# QCopterCAM_MCU_Sch.net
KiCad netlist of a schematic drawn in Altium Designer
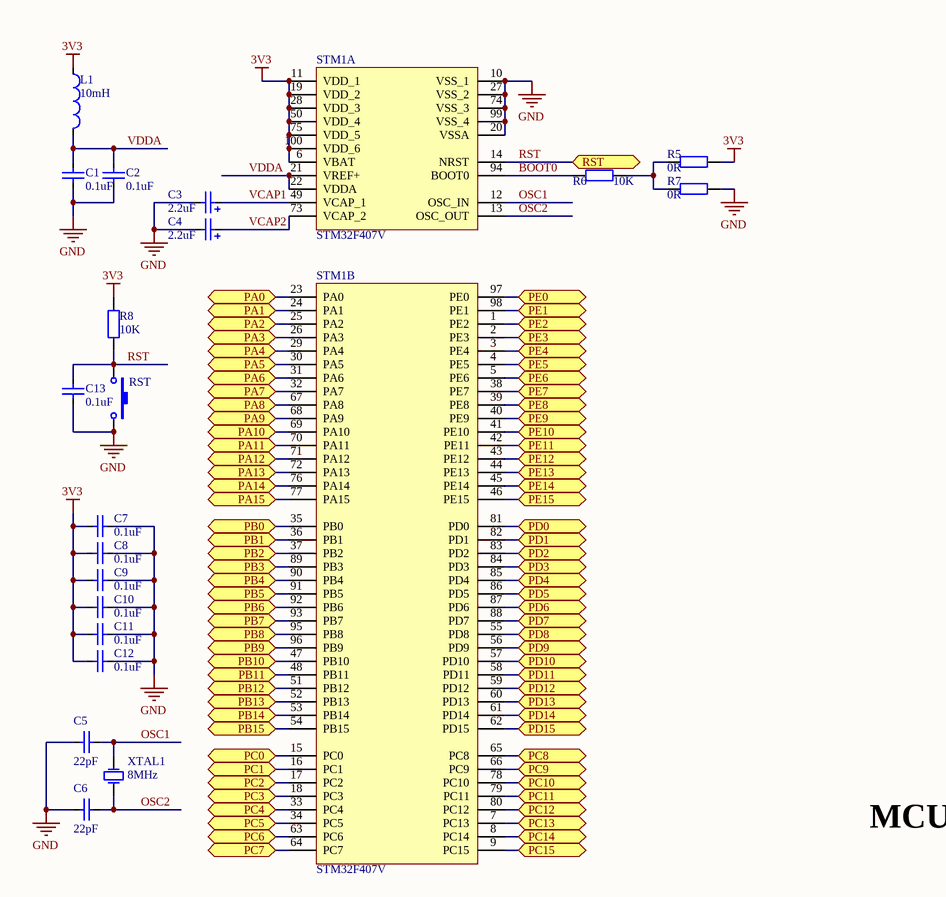
[diagram p0: QCopterCAM_MCU_Sch.SchDoc]

(export (version "E")
  (design (tool "Eeschema 10.0.6"))
  (components
    (comp (ref "C1")
      (value "0.1uF")
      (footprint "PCB_Passive:CAP_0603")
      (description "Capacitor")
      (fields (field (name "Comment") "Cap_0603"))
      (libsource (lib "SCH_Passive") (part "Cap_0603"))
    )
    (comp (ref "C2")
      (value "0.1uF")
      (footprint "PCB_Passive:CAP_0603")
      (description "Capacitor")
      (fields (field (name "Comment") "Cap_0603"))
      (libsource (lib "SCH_Passive") (part "Cap_0603"))
    )
    (comp (ref "C3")
      (value "2.2uF")
      (footprint "PCB_Passive:CAP_TAN_P0805")
      (description "Capacitor")
      (fields (field (name "Comment") "Cap_Tan_0805"))
      (libsource (lib "SCH_Passive") (part "Cap_Tan_0805"))
    )
    (comp (ref "C4")
      (value "2.2uF")
      (footprint "PCB_Passive:CAP_TAN_P0805")
      (description "Capacitor")
      (fields (field (name "Comment") "Cap_Tan_0805"))
      (libsource (lib "SCH_Passive") (part "Cap_Tan_0805"))
    )
    (comp (ref "C5")
      (value "22pF")
      (footprint "PCB_Passive:CAP_0603")
      (description "Capacitor")
      (fields (field (name "Comment") "Cap_0603"))
      (libsource (lib "SCH_Passive") (part "Cap_0603"))
    )
    (comp (ref "C6")
      (value "22pF")
      (footprint "PCB_Passive:CAP_0603")
      (description "Capacitor")
      (fields (field (name "Comment") "Cap_0603"))
      (libsource (lib "SCH_Passive") (part "Cap_0603"))
    )
    (comp (ref "C7")
      (value "0.1uF")
      (footprint "PCB_Passive:CAP_0603")
      (description "Capacitor")
      (fields (field (name "Comment") "Cap_0603"))
      (libsource (lib "SCH_Passive") (part "Cap_0603"))
    )
    (comp (ref "C8")
      (value "0.1uF")
      (footprint "PCB_Passive:CAP_0603")
      (description "Capacitor")
      (fields (field (name "Comment") "Cap_0603"))
      (libsource (lib "SCH_Passive") (part "Cap_0603"))
    )
    (comp (ref "C9")
      (value "0.1uF")
      (footprint "PCB_Passive:CAP_0603")
      (description "Capacitor")
      (fields (field (name "Comment") "Cap_0603"))
      (libsource (lib "SCH_Passive") (part "Cap_0603"))
    )
    (comp (ref "C10")
      (value "0.1uF")
      (footprint "PCB_Passive:CAP_0603")
      (description "Capacitor")
      (fields (field (name "Comment") "Cap_0603"))
      (libsource (lib "SCH_Passive") (part "Cap_0603"))
    )
    (comp (ref "C11")
      (value "0.1uF")
      (footprint "PCB_Passive:CAP_0603")
      (description "Capacitor")
      (fields (field (name "Comment") "Cap_0603"))
      (libsource (lib "SCH_Passive") (part "Cap_0603"))
    )
    (comp (ref "C12")
      (value "0.1uF")
      (footprint "PCB_Passive:CAP_0603")
      (description "Capacitor")
      (fields (field (name "Comment") "Cap_0603"))
      (libsource (lib "SCH_Passive") (part "Cap_0603"))
    )
    (comp (ref "C13")
      (value "0.1uF")
      (footprint "PCB_Passive:CAP_0603")
      (description "Capacitor")
      (fields (field (name "Comment") "Cap_0603"))
      (libsource (lib "SCH_Passive") (part "Cap_0603"))
    )
    (comp (ref "L1")
      (value "10mH")
      (footprint "PCB_Passive:IND_0603")
      (description "Inductor")
      (fields (field (name "Comment") "Ind_0603"))
      (libsource (lib "SCH_Passive") (part "Ind_0603"))
    )
    (comp (ref "R5")
      (value "0R")
      (footprint "PCB_Passive:RES_0603")
      (description "Resistor")
      (fields (field (name "Comment") "Res_0603"))
      (libsource (lib "") (part "Res_0603_1"))
    )
    (comp (ref "R6")
      (value "10K")
      (footprint "PCB_Passive:RES_0603")
      (description "Resistor")
      (fields (field (name "Comment") "Res_0603"))
      (libsource (lib "") (part "Res_0603_1"))
    )
    (comp (ref "R7")
      (value "0R")
      (footprint "PCB_Passive:RES_0603")
      (description "Resistor")
      (fields (field (name "Comment") "Res_0603"))
      (libsource (lib "") (part "Res_0603_1"))
    )
    (comp (ref "R8")
      (value "10K")
      (footprint "PCB_Passive:RES_0603")
      (description "Resistor")
      (fields (field (name "Comment") "Res_0603"))
      (libsource (lib "SCH_Passive") (part "Res_0603"))
    )
    (comp (ref "RST")
      (value "SW-PB_1")
      (footprint "PCB_Switch:BT_90_T")
      (description "Switch")
      (fields (field (name "PUBLISHER") "Altium Limited"))
      (libsource (lib "SCH_Switch") (part "SW-PB_1"))
    )
    (comp (ref "STM1")
      (value "STM32F407V")
      (footprint "PCB_IC:STM32F_100")
      (description "MCU")
      (libsource (lib "SCH_IC") (part "STM32F407V"))
    )
    (comp (ref "XTAL1")
      (value "8MHz")
      (footprint "PCB_Oscillator:XTAL_5032")
      (description "Crystal Oscillator")
      (fields (field (name "Comment") "XTAL_5032") (field (name "PUBLISHER") "Altium Limited"))
      (libsource (lib "SCH_Oscillator") (part "XTAL_5032"))
    )
  )
  (nets
    (net (code "1") (name "/BOOT0") (class "Default")
      (node (ref "R6") (pin "1") (pinfunction "1_1") (pintype "passive"))
      (node (ref "STM1") (pin "94") (pinfunction "BOOT0_94") (pintype "passive"))
    )
    (net (code "2") (name "/OSC1") (class "Default")
      (node (ref "C5") (pin "2") (pinfunction "2_2") (pintype "passive"))
      (node (ref "STM1") (pin "12") (pinfunction "OSC_IN_12") (pintype "passive"))
      (node (ref "XTAL1") (pin "2") (pinfunction "OSC2_2") (pintype "passive"))
    )
    (net (code "3") (name "/OSC2") (class "Default")
      (node (ref "C6") (pin "2") (pinfunction "2_2") (pintype "passive"))
      (node (ref "STM1") (pin "13") (pinfunction "OSC_OUT_13") (pintype "passive"))
      (node (ref "XTAL1") (pin "1") (pinfunction "OSC1_1") (pintype "passive"))
    )
    (net (code "4") (name "/PA0") (class "Default")
      (node (ref "STM1") (pin "23") (pinfunction "PA0_23") (pintype "passive"))
    )
    (net (code "5") (name "/PA1") (class "Default")
      (node (ref "STM1") (pin "24") (pinfunction "PA1_24") (pintype "passive"))
    )
    (net (code "6") (name "/PA2") (class "Default")
      (node (ref "STM1") (pin "25") (pinfunction "PA2_25") (pintype "passive"))
    )
    (net (code "7") (name "/PA3") (class "Default")
      (node (ref "STM1") (pin "26") (pinfunction "PA3_26") (pintype "passive"))
    )
    (net (code "8") (name "/PA4") (class "Default")
      (node (ref "STM1") (pin "29") (pinfunction "PA4_29") (pintype "passive"))
    )
    (net (code "9") (name "/PA5") (class "Default")
      (node (ref "STM1") (pin "30") (pinfunction "PA5_30") (pintype "passive"))
    )
    (net (code "10") (name "/PA6") (class "Default")
      (node (ref "STM1") (pin "31") (pinfunction "PA6_31") (pintype "passive"))
    )
    (net (code "11") (name "/PA7") (class "Default")
      (node (ref "STM1") (pin "32") (pinfunction "PA7_32") (pintype "passive"))
    )
    (net (code "12") (name "/PA8") (class "Default")
      (node (ref "STM1") (pin "67") (pinfunction "PA8_67") (pintype "passive"))
    )
    (net (code "13") (name "/PA9") (class "Default")
      (node (ref "STM1") (pin "68") (pinfunction "PA9_68") (pintype "passive"))
    )
    (net (code "14") (name "/PA10") (class "Default")
      (node (ref "STM1") (pin "69") (pinfunction "PA10_69") (pintype "passive"))
    )
    (net (code "15") (name "/PA11") (class "Default")
      (node (ref "STM1") (pin "70") (pinfunction "PA11_70") (pintype "passive"))
    )
    (net (code "16") (name "/PA12") (class "Default")
      (node (ref "STM1") (pin "71") (pinfunction "PA12_71") (pintype "passive"))
    )
    (net (code "17") (name "/PA13") (class "Default")
      (node (ref "STM1") (pin "72") (pinfunction "PA13_72") (pintype "passive"))
    )
    (net (code "18") (name "/PA14") (class "Default")
      (node (ref "STM1") (pin "76") (pinfunction "PA14_76") (pintype "passive"))
    )
    (net (code "19") (name "/PA15") (class "Default")
      (node (ref "STM1") (pin "77") (pinfunction "PA15_77") (pintype "passive"))
    )
    (net (code "20") (name "/PB0") (class "Default")
      (node (ref "STM1") (pin "35") (pinfunction "PB0_35") (pintype "passive"))
    )
    (net (code "21") (name "/PB1") (class "Default")
      (node (ref "STM1") (pin "36") (pinfunction "PB1_36") (pintype "passive"))
    )
    (net (code "22") (name "/PB2") (class "Default")
      (node (ref "STM1") (pin "37") (pinfunction "PB2_37") (pintype "passive"))
    )
    (net (code "23") (name "/PB3") (class "Default")
      (node (ref "STM1") (pin "89") (pinfunction "PB3_89") (pintype "passive"))
    )
    (net (code "24") (name "/PB4") (class "Default")
      (node (ref "STM1") (pin "90") (pinfunction "PB4_90") (pintype "passive"))
    )
    (net (code "25") (name "/PB5") (class "Default")
      (node (ref "STM1") (pin "91") (pinfunction "PB5_91") (pintype "passive"))
    )
    (net (code "26") (name "/PB6") (class "Default")
      (node (ref "STM1") (pin "92") (pinfunction "PB6_92") (pintype "passive"))
    )
    (net (code "27") (name "/PB7") (class "Default")
      (node (ref "STM1") (pin "93") (pinfunction "PB7_93") (pintype "passive"))
    )
    (net (code "28") (name "/PB8") (class "Default")
      (node (ref "STM1") (pin "95") (pinfunction "PB8_95") (pintype "passive"))
    )
    (net (code "29") (name "/PB9") (class "Default")
      (node (ref "STM1") (pin "96") (pinfunction "PB9_96") (pintype "passive"))
    )
    (net (code "30") (name "/PB10") (class "Default")
      (node (ref "STM1") (pin "47") (pinfunction "PB10_47") (pintype "passive"))
    )
    (net (code "31") (name "/PB11") (class "Default")
      (node (ref "STM1") (pin "48") (pinfunction "PB11_48") (pintype "passive"))
    )
    (net (code "32") (name "/PB12") (class "Default")
      (node (ref "STM1") (pin "51") (pinfunction "PB12_51") (pintype "passive"))
    )
    (net (code "33") (name "/PB13") (class "Default")
      (node (ref "STM1") (pin "52") (pinfunction "PB13_52") (pintype "passive"))
    )
    (net (code "34") (name "/PB14") (class "Default")
      (node (ref "STM1") (pin "53") (pinfunction "PB14_53") (pintype "passive"))
    )
    (net (code "35") (name "/PB15") (class "Default")
      (node (ref "STM1") (pin "54") (pinfunction "PB15_54") (pintype "passive"))
    )
    (net (code "36") (name "/PC0") (class "Default")
      (node (ref "STM1") (pin "15") (pinfunction "PC0_15") (pintype "passive"))
    )
    (net (code "37") (name "/PC1") (class "Default")
      (node (ref "STM1") (pin "16") (pinfunction "PC1_16") (pintype "passive"))
    )
    (net (code "38") (name "/PC2") (class "Default")
      (node (ref "STM1") (pin "17") (pinfunction "PC2_17") (pintype "passive"))
    )
    (net (code "39") (name "/PC3") (class "Default")
      (node (ref "STM1") (pin "18") (pinfunction "PC3_18") (pintype "passive"))
    )
    (net (code "40") (name "/PC4") (class "Default")
      (node (ref "STM1") (pin "33") (pinfunction "PC4_33") (pintype "passive"))
    )
    (net (code "41") (name "/PC5") (class "Default")
      (node (ref "STM1") (pin "34") (pinfunction "PC5_34") (pintype "passive"))
    )
    (net (code "42") (name "/PC6") (class "Default")
      (node (ref "STM1") (pin "63") (pinfunction "PC6_63") (pintype "passive"))
    )
    (net (code "43") (name "/PC7") (class "Default")
      (node (ref "STM1") (pin "64") (pinfunction "PC7_64") (pintype "passive"))
    )
    (net (code "44") (name "/PC8") (class "Default")
      (node (ref "STM1") (pin "65") (pinfunction "PC8_65") (pintype "passive"))
    )
    (net (code "45") (name "/PC9") (class "Default")
      (node (ref "STM1") (pin "66") (pinfunction "PC9_66") (pintype "passive"))
    )
    (net (code "46") (name "/PC10") (class "Default")
      (node (ref "STM1") (pin "78") (pinfunction "PC10_78") (pintype "passive"))
    )
    (net (code "47") (name "/PC11") (class "Default")
      (node (ref "STM1") (pin "79") (pinfunction "PC11_79") (pintype "passive"))
    )
    (net (code "48") (name "/PC12") (class "Default")
      (node (ref "STM1") (pin "80") (pinfunction "PC12_80") (pintype "passive"))
    )
    (net (code "49") (name "/PC13") (class "Default")
      (node (ref "STM1") (pin "7") (pinfunction "PC13_7") (pintype "passive"))
    )
    (net (code "50") (name "/PC14") (class "Default")
      (node (ref "STM1") (pin "8") (pinfunction "PC14_8") (pintype "passive"))
    )
    (net (code "51") (name "/PC15") (class "Default")
      (node (ref "STM1") (pin "9") (pinfunction "PC15_9") (pintype "passive"))
    )
    (net (code "52") (name "/PD0") (class "Default")
      (node (ref "STM1") (pin "81") (pinfunction "PD0_81") (pintype "passive"))
    )
    (net (code "53") (name "/PD1") (class "Default")
      (node (ref "STM1") (pin "82") (pinfunction "PD1_82") (pintype "passive"))
    )
    (net (code "54") (name "/PD2") (class "Default")
      (node (ref "STM1") (pin "83") (pinfunction "PD2_83") (pintype "passive"))
    )
    (net (code "55") (name "/PD3") (class "Default")
      (node (ref "STM1") (pin "84") (pinfunction "PD3_84") (pintype "passive"))
    )
    (net (code "56") (name "/PD4") (class "Default")
      (node (ref "STM1") (pin "85") (pinfunction "PD4_85") (pintype "passive"))
    )
    (net (code "57") (name "/PD5") (class "Default")
      (node (ref "STM1") (pin "86") (pinfunction "PD5_86") (pintype "passive"))
    )
    (net (code "58") (name "/PD6") (class "Default")
      (node (ref "STM1") (pin "87") (pinfunction "PD6_87") (pintype "passive"))
    )
    (net (code "59") (name "/PD7") (class "Default")
      (node (ref "STM1") (pin "88") (pinfunction "PD7_88") (pintype "passive"))
    )
    (net (code "60") (name "/PD8") (class "Default")
      (node (ref "STM1") (pin "55") (pinfunction "PD8_55") (pintype "passive"))
    )
    (net (code "61") (name "/PD9") (class "Default")
      (node (ref "STM1") (pin "56") (pinfunction "PD9_56") (pintype "passive"))
    )
    (net (code "62") (name "/PD10") (class "Default")
      (node (ref "STM1") (pin "57") (pinfunction "PD10_57") (pintype "passive"))
    )
    (net (code "63") (name "/PD11") (class "Default")
      (node (ref "STM1") (pin "58") (pinfunction "PD11_58") (pintype "passive"))
    )
    (net (code "64") (name "/PD12") (class "Default")
      (node (ref "STM1") (pin "59") (pinfunction "PD12_59") (pintype "passive"))
    )
    (net (code "65") (name "/PD13") (class "Default")
      (node (ref "STM1") (pin "60") (pinfunction "PD13_60") (pintype "passive"))
    )
    (net (code "66") (name "/PD14") (class "Default")
      (node (ref "STM1") (pin "61") (pinfunction "PD14_61") (pintype "passive"))
    )
    (net (code "67") (name "/PD15") (class "Default")
      (node (ref "STM1") (pin "62") (pinfunction "PD15_62") (pintype "passive"))
    )
    (net (code "68") (name "/PE0") (class "Default")
      (node (ref "STM1") (pin "97") (pinfunction "PE0_97") (pintype "passive"))
    )
    (net (code "69") (name "/PE1") (class "Default")
      (node (ref "STM1") (pin "98") (pinfunction "PE1_98") (pintype "passive"))
    )
    (net (code "70") (name "/PE2") (class "Default")
      (node (ref "STM1") (pin "1") (pinfunction "PE2_1") (pintype "passive"))
    )
    (net (code "71") (name "/PE3") (class "Default")
      (node (ref "STM1") (pin "2") (pinfunction "PE3_2") (pintype "passive"))
    )
    (net (code "72") (name "/PE4") (class "Default")
      (node (ref "STM1") (pin "3") (pinfunction "PE4_3") (pintype "passive"))
    )
    (net (code "73") (name "/PE5") (class "Default")
      (node (ref "STM1") (pin "4") (pinfunction "PE5_4") (pintype "passive"))
    )
    (net (code "74") (name "/PE6") (class "Default")
      (node (ref "STM1") (pin "5") (pinfunction "PE6_5") (pintype "passive"))
    )
    (net (code "75") (name "/PE7") (class "Default")
      (node (ref "STM1") (pin "38") (pinfunction "PE7_38") (pintype "passive"))
    )
    (net (code "76") (name "/PE8") (class "Default")
      (node (ref "STM1") (pin "39") (pinfunction "PE8_39") (pintype "passive"))
    )
    (net (code "77") (name "/PE9") (class "Default")
      (node (ref "STM1") (pin "40") (pinfunction "PE9_40") (pintype "passive"))
    )
    (net (code "78") (name "/PE10") (class "Default")
      (node (ref "STM1") (pin "41") (pinfunction "PE10_41") (pintype "passive"))
    )
    (net (code "79") (name "/PE11") (class "Default")
      (node (ref "STM1") (pin "42") (pinfunction "PE11_42") (pintype "passive"))
    )
    (net (code "80") (name "/PE12") (class "Default")
      (node (ref "STM1") (pin "43") (pinfunction "PE12_43") (pintype "passive"))
    )
    (net (code "81") (name "/PE13") (class "Default")
      (node (ref "STM1") (pin "44") (pinfunction "PE13_44") (pintype "passive"))
    )
    (net (code "82") (name "/PE14") (class "Default")
      (node (ref "STM1") (pin "45") (pinfunction "PE14_45") (pintype "passive"))
    )
    (net (code "83") (name "/PE15") (class "Default")
      (node (ref "STM1") (pin "46") (pinfunction "PE15_46") (pintype "passive"))
    )
    (net (code "84") (name "/RST") (class "Default")
      (node (ref "C13") (pin "1") (pinfunction "1_1") (pintype "passive"))
      (node (ref "R8") (pin "2") (pinfunction "2_2") (pintype "passive"))
      (node (ref "RST") (pin "1") (pinfunction "1_1") (pintype "passive"))
      (node (ref "STM1") (pin "14") (pinfunction "NRST_14") (pintype "passive"))
    )
    (net (code "85") (name "/VCAP1") (class "Default")
      (node (ref "C3") (pin "1") (pinfunction "1_1") (pintype "passive"))
      (node (ref "STM1") (pin "49") (pinfunction "VCAP_1_49") (pintype "passive"))
    )
    (net (code "86") (name "/VCAP2") (class "Default")
      (node (ref "C4") (pin "1") (pinfunction "1_1") (pintype "passive"))
      (node (ref "STM1") (pin "73") (pinfunction "VCAP_2_73") (pintype "passive"))
    )
    (net (code "87") (name "/VDDA") (class "Default")
      (node (ref "C1") (pin "1") (pinfunction "1_1") (pintype "passive"))
      (node (ref "C2") (pin "1") (pinfunction "1_1") (pintype "passive"))
      (node (ref "L1") (pin "2") (pinfunction "2_2") (pintype "passive"))
      (node (ref "STM1") (pin "21") (pinfunction "VREF+_21") (pintype "passive"))
      (node (ref "STM1") (pin "22") (pinfunction "VDDA_22") (pintype "passive"))
    )
    (net (code "88") (name "3V3") (class "Default")
      (node (ref "C10") (pin "2") (pinfunction "2_2") (pintype "passive"))
      (node (ref "C11") (pin "2") (pinfunction "2_2") (pintype "passive"))
      (node (ref "C12") (pin "2") (pinfunction "2_2") (pintype "passive"))
      (node (ref "C7") (pin "2") (pinfunction "2_2") (pintype "passive"))
      (node (ref "C8") (pin "2") (pinfunction "2_2") (pintype "passive"))
      (node (ref "C9") (pin "2") (pinfunction "2_2") (pintype "passive"))
      (node (ref "L1") (pin "1") (pinfunction "1_1") (pintype "passive"))
      (node (ref "R5") (pin "2") (pinfunction "2_2") (pintype "passive"))
      (node (ref "R8") (pin "1") (pinfunction "1_1") (pintype "passive"))
      (node (ref "STM1") (pin "100") (pinfunction "VDD_6_100") (pintype "passive"))
      (node (ref "STM1") (pin "11") (pinfunction "VDD_1_11") (pintype "passive"))
      (node (ref "STM1") (pin "19") (pinfunction "VDD_2_19") (pintype "passive"))
      (node (ref "STM1") (pin "28") (pinfunction "VDD_3_28") (pintype "passive"))
      (node (ref "STM1") (pin "50") (pinfunction "VDD_4_50") (pintype "passive"))
      (node (ref "STM1") (pin "6") (pinfunction "VBAT_6") (pintype "passive"))
      (node (ref "STM1") (pin "75") (pinfunction "VDD_5_75") (pintype "passive"))
    )
    (net (code "89") (name "GND") (class "Default")
      (node (ref "C1") (pin "2") (pinfunction "2_2") (pintype "passive"))
      (node (ref "C10") (pin "1") (pinfunction "1_1") (pintype "passive"))
      (node (ref "C11") (pin "1") (pinfunction "1_1") (pintype "passive"))
      (node (ref "C12") (pin "1") (pinfunction "1_1") (pintype "passive"))
      (node (ref "C13") (pin "2") (pinfunction "2_2") (pintype "passive"))
      (node (ref "C2") (pin "2") (pinfunction "2_2") (pintype "passive"))
      (node (ref "C3") (pin "2") (pinfunction "2_2") (pintype "passive"))
      (node (ref "C4") (pin "2") (pinfunction "2_2") (pintype "passive"))
      (node (ref "C5") (pin "1") (pinfunction "1_1") (pintype "passive"))
      (node (ref "C6") (pin "1") (pinfunction "1_1") (pintype "passive"))
      (node (ref "C7") (pin "1") (pinfunction "1_1") (pintype "passive"))
      (node (ref "C8") (pin "1") (pinfunction "1_1") (pintype "passive"))
      (node (ref "C9") (pin "1") (pinfunction "1_1") (pintype "passive"))
      (node (ref "R7") (pin "2") (pinfunction "2_2") (pintype "passive"))
      (node (ref "RST") (pin "2") (pinfunction "2_2") (pintype "passive"))
      (node (ref "STM1") (pin "10") (pinfunction "VSS_1_10") (pintype "passive"))
      (node (ref "STM1") (pin "20") (pinfunction "VSSA_20") (pintype "passive"))
      (node (ref "STM1") (pin "27") (pinfunction "VSS_2_27") (pintype "passive"))
      (node (ref "STM1") (pin "74") (pinfunction "VSS_3_74") (pintype "passive"))
      (node (ref "STM1") (pin "99") (pinfunction "VSS_4_99") (pintype "passive"))
    )
    (net (code "90") (name "Net-(R5-Pad1)") (class "Default")
      (node (ref "R5") (pin "1") (pinfunction "1_1") (pintype "passive"))
      (node (ref "R6") (pin "2") (pinfunction "2_2") (pintype "passive"))
      (node (ref "R7") (pin "1") (pinfunction "1_1") (pintype "passive"))
    )
  )
)
